# Fri3D_2024_01.net
KiCad netlist of a schematic drawn in Altium Designer
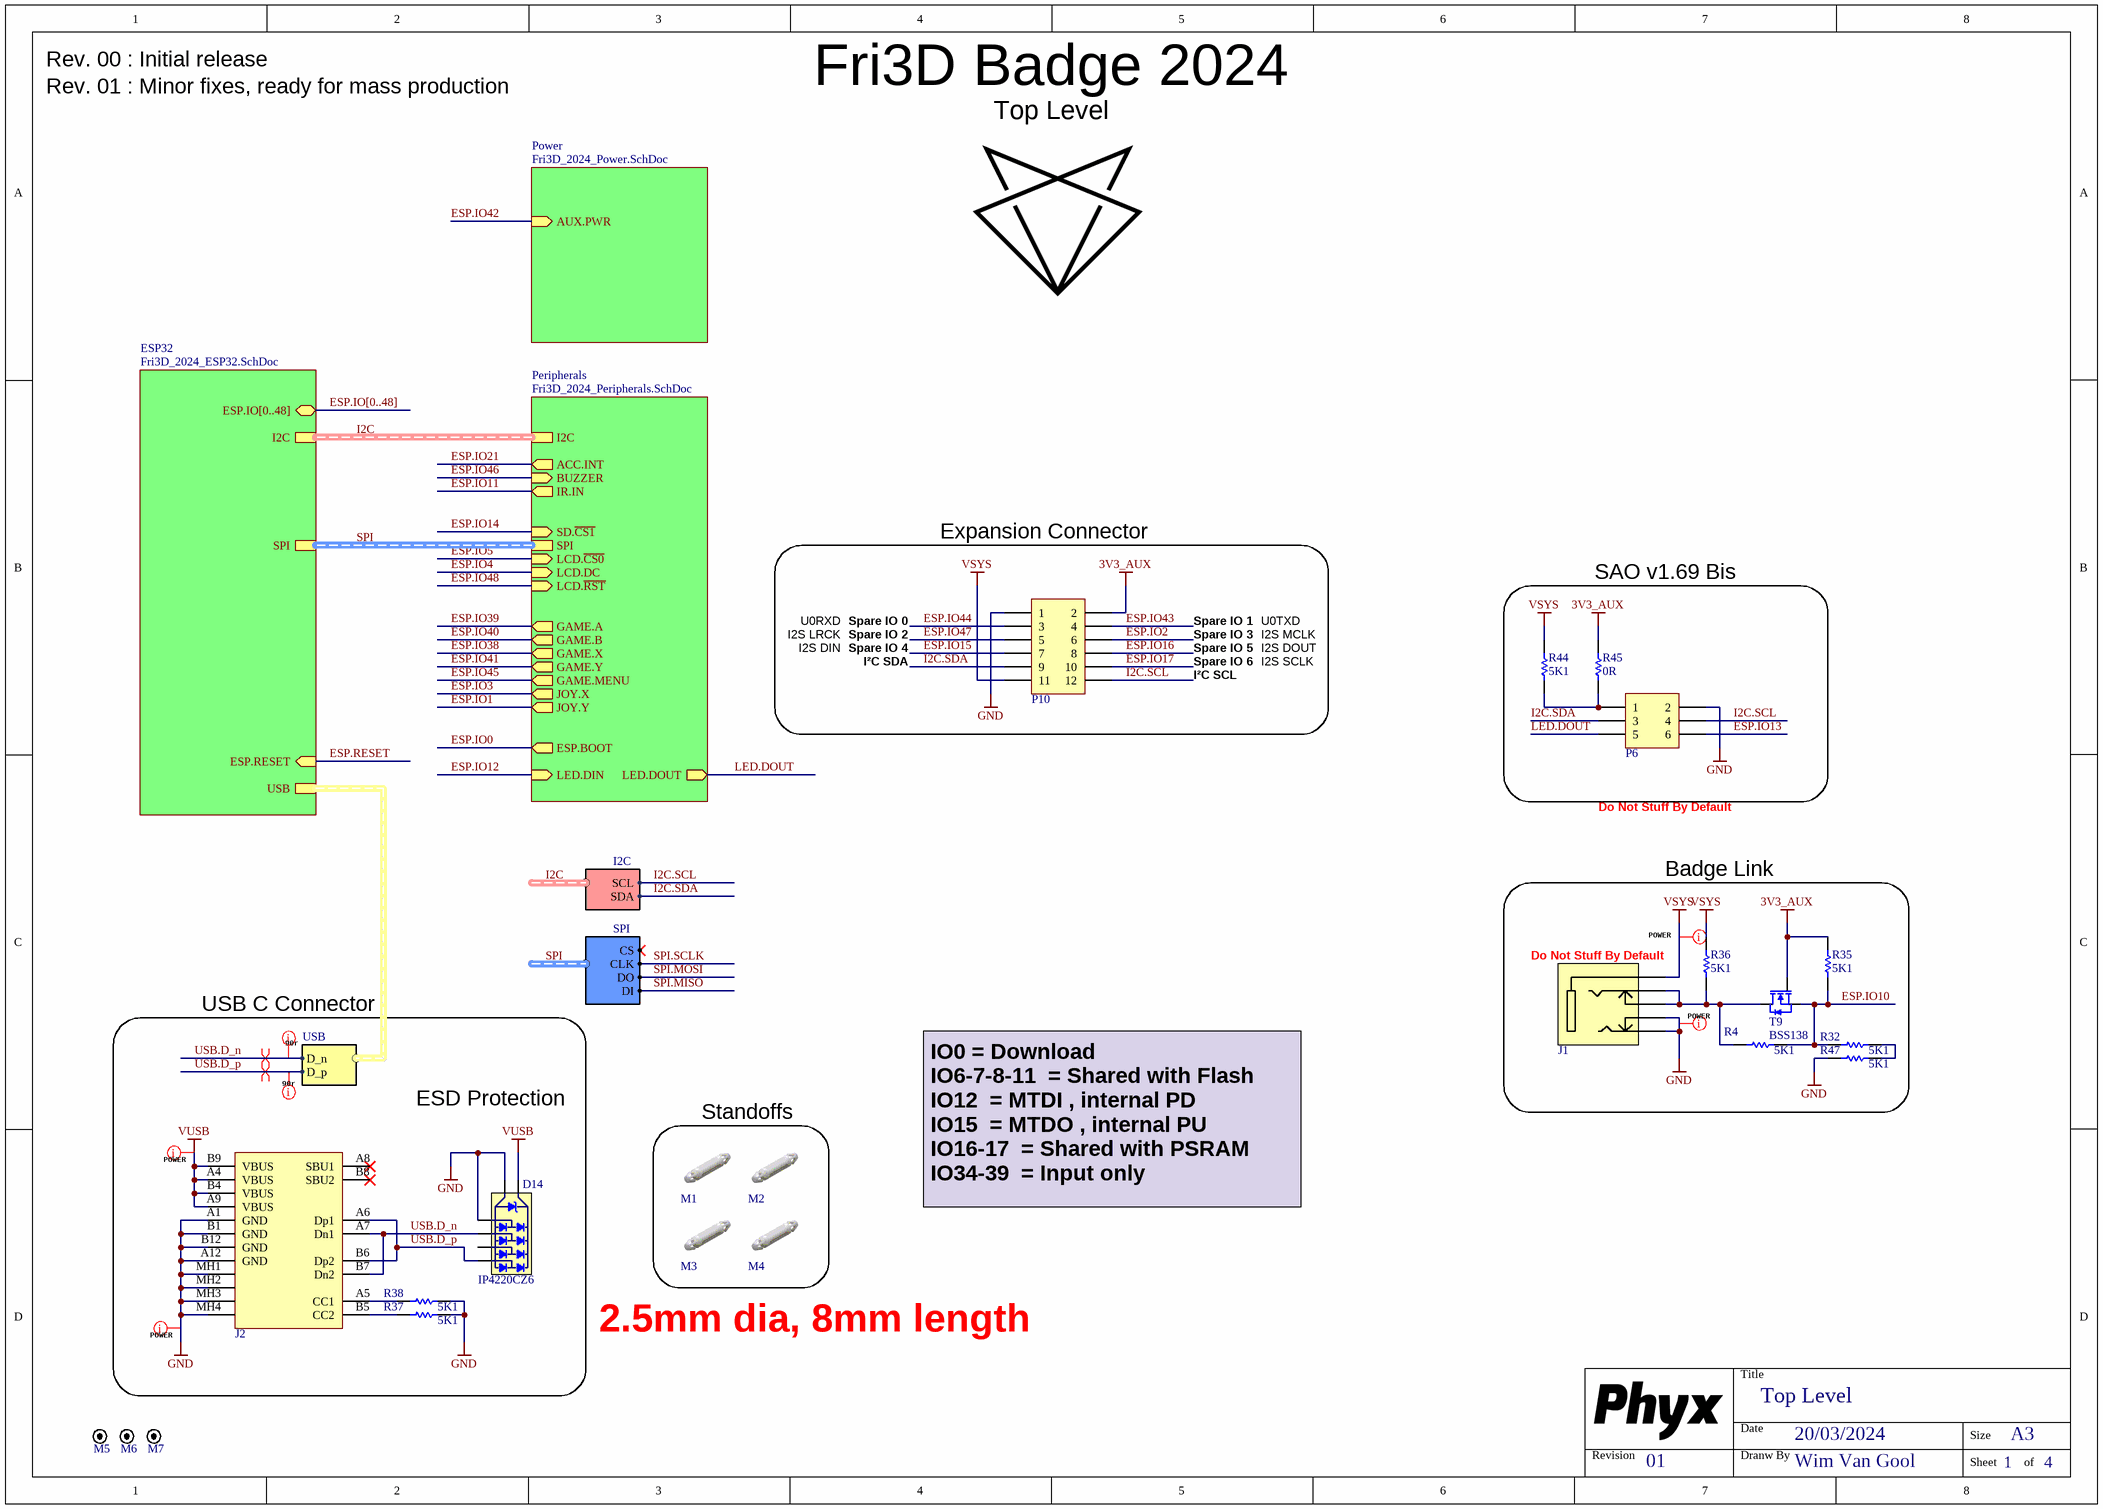
[diagram p0: Fri3D_2024_01.SchDoc]

(export (version "E")
  (design (tool "Eeschema 10.0.6"))
  (components
    (comp (ref "D14")
      (value "IP4220CZ6")
      (footprint "NXP_SOT457")
      (description "=Description")
      (fields (field (name "Comment") "TVS Diode Dual USB"))
      (libsource (lib "Phyx_Components") (part "NXP_IP4220CZ6"))
    )
    (comp (ref "J1")
      (value "3.5mm jack, dual switch, black, 3 contacts")
      (footprint "CUI_SJ1-3525NG")
      (description "=Description")
      (libsource (lib "Phyx_Components") (part "CUI_SJ1-3525NG"))
    )
    (comp (ref "J2")
      (value "USB 2.0 C Reversible Receptacle Horizontal full SMD")
      (footprint "XUNPU-TYPEC-304S-ACP16")
      (libsource (lib "Phyx_Components") (part "USB_C_16_4"))
    )
    (comp (ref "M1")
      (value "HIWA LCC-12 Snap-in - Snap-in 12.7mm")
      (footprint "WE_709622400")
      (libsource (lib "Phyx_Components") (part "WE_SNSN"))
    )
    (comp (ref "M2")
      (value "HIWA LCC-12 Snap-in - Snap-in 12.7mm")
      (footprint "WE_709622400")
      (libsource (lib "Phyx_Components") (part "WE_SNSN"))
    )
    (comp (ref "M3")
      (value "HIWA LCC-12 Snap-in - Snap-in 12.7mm")
      (footprint "WE_709622400")
      (libsource (lib "Phyx_Components") (part "WE_SNSN"))
    )
    (comp (ref "M4")
      (value "HIWA LCC-12 Snap-in - Snap-in 12.7mm")
      (footprint "WE_709622400")
      (libsource (lib "Phyx_Components") (part "WE_SNSN"))
    )
    (comp (ref "M5")
      (value "Fiducial 0.5mm")
      (footprint "FID_0.5mm")
      (description "FIDUCIAL")
      (libsource (lib "Phyx_Components") (part "FIDUCIAL"))
    )
    (comp (ref "M6")
      (value "Fiducial 0.5mm")
      (footprint "FID_0.5mm")
      (description "FIDUCIAL")
      (libsource (lib "Phyx_Components") (part "FIDUCIAL"))
    )
    (comp (ref "M7")
      (value "Fiducial 0.5mm")
      (footprint "FID_0.5mm")
      (description "FIDUCIAL")
      (libsource (lib "Phyx_Components") (part "FIDUCIAL"))
    )
    (comp (ref "P6")
      (value "Receptacle 3x2")
      (footprint "RCPT2X3")
      (libsource (lib "Phyx_Components") (part "Header 3X2"))
    )
    (comp (ref "P10")
      (value "Receptacle 6x2 SMD low profile")
      (footprint "WE_610312243021_POST")
      (libsource (lib "Phyx_Components") (part "Header 6X2"))
    )
    (comp (ref "R4")
      (value "5K1")
      (footprint "R0603_N")
      (fields (field (name "Comment") "RESISTOR"))
      (libsource (lib "Phyx_Components") (part "RESISTOR"))
    )
    (comp (ref "R32")
      (value "5K1")
      (footprint "R0603_N")
      (fields (field (name "Comment") "RESISTOR"))
      (libsource (lib "Phyx_Components") (part "RESISTOR"))
    )
    (comp (ref "R35")
      (value "5K1")
      (footprint "R0603_N")
      (fields (field (name "Comment") "RESISTOR"))
      (libsource (lib "Phyx_Components") (part "RESISTOR"))
    )
    (comp (ref "R36")
      (value "5K1")
      (footprint "R0603_N")
      (fields (field (name "Comment") "RESISTOR"))
      (libsource (lib "Phyx_Components") (part "RESISTOR"))
    )
    (comp (ref "R37")
      (value "5K1")
      (footprint "R0603_N")
      (fields (field (name "Comment") "RESISTOR"))
      (libsource (lib "Phyx_Components") (part "RESISTOR"))
    )
    (comp (ref "R38")
      (value "5K1")
      (footprint "R0603_N")
      (fields (field (name "Comment") "RESISTOR"))
      (libsource (lib "Phyx_Components") (part "RESISTOR"))
    )
    (comp (ref "R44")
      (value "5K1")
      (footprint "R0603_N")
      (fields (field (name "Comment") "RESISTOR"))
      (libsource (lib "Phyx_Components") (part "RESISTOR"))
    )
    (comp (ref "R45")
      (value "0R")
      (footprint "R0603_N")
      (fields (field (name "Comment") "RESISTOR"))
      (libsource (lib "Phyx_Components") (part "RESISTOR"))
    )
    (comp (ref "R47")
      (value "5K1")
      (footprint "R0603_N")
      (fields (field (name "Comment") "RESISTOR"))
      (libsource (lib "Phyx_Components") (part "RESISTOR"))
    )
    (comp (ref "T9")
      (value "BSS138")
      (footprint "SOT23-3")
      (fields (field (name "Comment") "0.2A N-Ch MOSFET Vgs 3.2"))
      (libsource (lib "Phyx_Components") (part "N_MOSFET_GSD"))
    )
  )
  (nets
    (net (code "32") (name "/ESP.IO2") (class "Default")
      (node (ref "P10") (pin "6") (pinfunction "6_6") (pintype "passive"))
    )
    (net (code "36") (name "/ESP.IO10") (class "Default")
      (node (ref "R32") (pin "2") (pinfunction "2_2") (pintype "passive"))
      (node (ref "R35") (pin "2") (pinfunction "2_2") (pintype "passive"))
      (node (ref "R4") (pin "1") (pinfunction "1_1") (pintype "passive"))
      (node (ref "T9") (pin "2") (pinfunction "S_2") (pintype "passive"))
    )
    (net (code "39") (name "/ESP.IO13") (class "Default")
      (node (ref "P6") (pin "6") (pinfunction "6_6") (pintype "passive"))
    )
    (net (code "41") (name "/ESP.IO15") (class "Default")
      (node (ref "P10") (pin "7") (pinfunction "7_7") (pintype "passive"))
    )
    (net (code "42") (name "/ESP.IO16") (class "Default")
      (node (ref "P10") (pin "8") (pinfunction "8_8") (pintype "passive"))
    )
    (net (code "43") (name "/ESP.IO17") (class "Default")
      (node (ref "P10") (pin "10") (pinfunction "10_10") (pintype "passive"))
    )
    (net (code "50") (name "/ESP.IO43") (class "Default")
      (node (ref "P10") (pin "4") (pinfunction "4_4") (pintype "passive"))
    )
    (net (code "51") (name "/ESP.IO44") (class "Default")
      (node (ref "P10") (pin "3") (pinfunction "3_3") (pintype "passive"))
    )
    (net (code "54") (name "/ESP.IO47") (class "Default")
      (node (ref "P10") (pin "5") (pinfunction "5_5") (pintype "passive"))
    )
    (net (code "58") (name "/I2C.SCL") (class "Default")
      (node (ref "P10") (pin "12") (pinfunction "12_12") (pintype "passive"))
      (node (ref "P6") (pin "4") (pinfunction "4_4") (pintype "passive"))
    )
    (net (code "59") (name "/I2C.SDA") (class "Default")
      (node (ref "P10") (pin "9") (pinfunction "9_9") (pintype "passive"))
      (node (ref "P6") (pin "3") (pinfunction "3_3") (pintype "passive"))
    )
    (net (code "61") (name "/LED.DOUT") (class "Default")
      (node (ref "P6") (pin "5") (pinfunction "5_5") (pintype "passive"))
    )
    (net (code "66") (name "/USB.D_n") (class "Default")
      (node (ref "D14") (pin "1") (pinfunction "1_1") (pintype "passive"))
      (node (ref "J2") (pin "A7") (pinfunction "Dn1_A7") (pintype "passive"))
      (node (ref "J2") (pin "B7") (pinfunction "Dn2_B7") (pintype "passive"))
    )
    (net (code "67") (name "/USB.D_p") (class "Default")
      (node (ref "D14") (pin "6") (pinfunction "6_6") (pintype "passive"))
      (node (ref "J2") (pin "A6") (pinfunction "Dp1_A6") (pintype "passive"))
      (node (ref "J2") (pin "B6") (pinfunction "Dp2_B6") (pintype "passive"))
    )
    (net (code "71") (name "3V3_AUX") (class "Default")
      (node (ref "P10") (pin "2") (pinfunction "2_2") (pintype "passive"))
      (node (ref "R35") (pin "1") (pinfunction "1_1") (pintype "passive"))
      (node (ref "R45") (pin "1") (pinfunction "1_1") (pintype "passive"))
      (node (ref "T9") (pin "1") (pinfunction "G_1") (pintype "passive"))
    )
    (net (code "72") (name "GND") (class "Default")
      (node (ref "D14") (pin "2") (pinfunction "GND_2") (pintype "passive"))
      (node (ref "D14") (pin "3") (pinfunction "3_3") (pintype "passive"))
      (node (ref "J1") (pin "2") (pinfunction "Tip_2") (pintype "passive"))
      (node (ref "J1") (pin "4") (pinfunction "4_4") (pintype "passive"))
      (node (ref "J2") (pin "A1") (pinfunction "GND_A1") (pintype "passive"))
      (node (ref "J2") (pin "A12") (pinfunction "GND_A12") (pintype "passive"))
      (node (ref "J2") (pin "B1") (pinfunction "GND_B1") (pintype "passive"))
      (node (ref "J2") (pin "B12") (pinfunction "GND_B12") (pintype "passive"))
      (node (ref "J2") (pin "MH1") (pinfunction "Tab_MH1") (pintype "passive"))
      (node (ref "J2") (pin "MH2") (pinfunction "Tab_MH2") (pintype "passive"))
      (node (ref "J2") (pin "MH3") (pinfunction "Tab_MH3") (pintype "passive"))
      (node (ref "J2") (pin "MH4") (pinfunction "Tab_MH4") (pintype "passive"))
      (node (ref "P10") (pin "1") (pinfunction "1_1") (pintype "passive"))
      (node (ref "P6") (pin "2") (pinfunction "2_2") (pintype "passive"))
      (node (ref "R37") (pin "2") (pinfunction "2_2") (pintype "passive"))
      (node (ref "R38") (pin "2") (pinfunction "2_2") (pintype "passive"))
      (node (ref "R47") (pin "2") (pinfunction "2_2") (pintype "passive"))
    )
    (net (code "73") (name "Net-(J1-Ring)") (class "Default")
      (node (ref "J1") (pin "3") (pinfunction "Ring_3") (pintype "passive"))
      (node (ref "J1") (pin "5") (pinfunction "5_5") (pintype "passive"))
      (node (ref "R36") (pin "2") (pinfunction "2_2") (pintype "passive"))
      (node (ref "R4") (pin "2") (pinfunction "2_2") (pintype "passive"))
      (node (ref "T9") (pin "3") (pinfunction "D_3") (pintype "passive"))
    )
    (net (code "74") (name "Net-(J2-CC1)") (class "Default")
      (node (ref "J2") (pin "A5") (pinfunction "CC1_A5") (pintype "passive"))
      (node (ref "R38") (pin "1") (pinfunction "1_1") (pintype "passive"))
    )
    (net (code "75") (name "Net-(J2-CC2)") (class "Default")
      (node (ref "J2") (pin "B5") (pinfunction "CC2_B5") (pintype "passive"))
      (node (ref "R37") (pin "1") (pinfunction "1_1") (pintype "passive"))
    )
    (net (code "76") (name "Net-(P6-Pad1)") (class "Default")
      (node (ref "P6") (pin "1") (pinfunction "1_1") (pintype "passive"))
      (node (ref "R44") (pin "1") (pinfunction "1_1") (pintype "passive"))
      (node (ref "R45") (pin "2") (pinfunction "2_2") (pintype "passive"))
    )
    (net (code "77") (name "Net-(R32-Pad1)") (class "Default")
      (node (ref "R32") (pin "1") (pinfunction "1_1") (pintype "passive"))
      (node (ref "R47") (pin "1") (pinfunction "1_1") (pintype "passive"))
    )
    (net (code "78") (name "VSYS") (class "Default")
      (node (ref "J1") (pin "1") (pinfunction "Sleeve_1") (pintype "passive"))
      (node (ref "P10") (pin "11") (pinfunction "11_11") (pintype "passive"))
      (node (ref "R36") (pin "1") (pinfunction "1_1") (pintype "passive"))
      (node (ref "R44") (pin "2") (pinfunction "2_2") (pintype "passive"))
    )
    (net (code "79") (name "VUSB") (class "Default")
      (node (ref "D14") (pin "5") (pinfunction "VBus_5") (pintype "passive"))
      (node (ref "J2") (pin "A4") (pinfunction "VBUS_A4") (pintype "passive"))
      (node (ref "J2") (pin "A9") (pinfunction "VBUS_A9") (pintype "passive"))
      (node (ref "J2") (pin "B4") (pinfunction "VBUS_B4") (pintype "passive"))
      (node (ref "J2") (pin "B9") (pinfunction "VBUS_B9") (pintype "passive"))
    )
    (net (code "80") (name "unconnected-(D14-Pad4)") (class "Default")
      (node (ref "D14") (pin "4") (pinfunction "4_4") (pintype "passive"))
    )
    (net (code "81") (name "unconnected-(J2-SBU1-PadA8)") (class "Default")
      (node (ref "J2") (pin "A8") (pinfunction "SBU1_A8") (pintype "passive+no_connect"))
    )
    (net (code "82") (name "unconnected-(J2-SBU2-PadB8)") (class "Default")
      (node (ref "J2") (pin "B8") (pinfunction "SBU2_B8") (pintype "passive+no_connect"))
    )
  )
)
